# Schema.net
KiCad netlist of a schematic drawn in Altium Designer
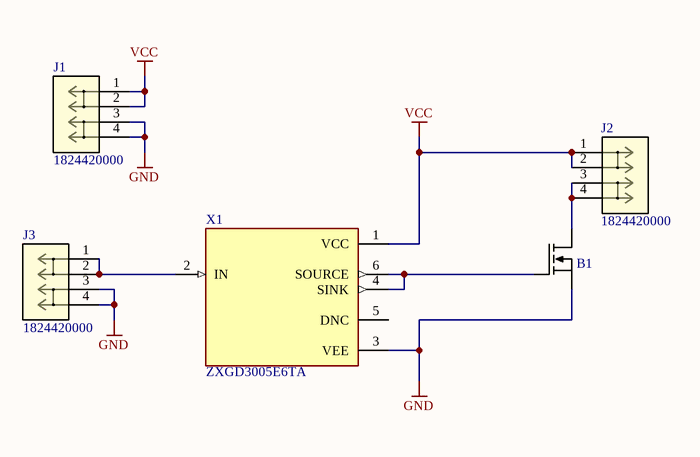
[diagram p0: Schema.SchDoc]

(export (version "E")
  (design (tool "Eeschema 10.0.6"))
  (components
    (comp (ref "B1")
      (value "N Kanal FET")
      (footprint "GeneralPCBLibrary:SOT23-3")
      (libsource (lib "GeneralSchemaLibrary") (part "N Kanal FET"))
    )
    (comp (ref "J1")
      (value "1824420000")
      (footprint "CONN2_1824420000_WED")
      (description "No Description Available")
      (fields (field (name "COPYRIGHT") "Copyright (C) 2021 Ultra Librarian. All rights reserved."))
      (libsource (lib "GeneralSchemaLibrary") (part "1824420000"))
    )
    (comp (ref "J2")
      (value "1824420000")
      (footprint "CONN2_1824420000_WED")
      (description "No Description Available")
      (fields (field (name "COPYRIGHT") "Copyright (C) 2021 Ultra Librarian. All rights reserved."))
      (libsource (lib "") (part "1824420000_1"))
    )
    (comp (ref "J3")
      (value "1824420000")
      (footprint "CONN2_1824420000_WED")
      (description "No Description Available")
      (fields (field (name "COPYRIGHT") "Copyright (C) 2021 Ultra Librarian. All rights reserved."))
      (libsource (lib "GeneralSchemaLibrary") (part "1824420000"))
    )
    (comp (ref "X1")
      (value "ZXGD3005E6TA")
      (footprint "GeneralPCBLibrary:SOT26")
      (description "Low-Side Gate Driver IC Non-Inverting SOT-26")
      (libsource (lib "GeneralSchemaLibrary") (part "ZXGD3005E6TA"))
    )
  )
  (nets
    (net (code "1") (name "GND") (class "Default")
      (node (ref "B1") (pin "2") (pinfunction "Source_2") (pintype "passive"))
      (node (ref "J1") (pin "3") (pinfunction "3_3") (pintype "passive"))
      (node (ref "J1") (pin "4") (pinfunction "4_4") (pintype "passive"))
      (node (ref "J3") (pin "3") (pinfunction "3_3") (pintype "passive"))
      (node (ref "J3") (pin "4") (pinfunction "4_4") (pintype "passive"))
      (node (ref "X1") (pin "3") (pinfunction "VEE_3") (pintype "power_in"))
    )
    (net (code "2") (name "Net-(B1-Drain)") (class "Default")
      (node (ref "B1") (pin "3") (pinfunction "Drain_3") (pintype "passive"))
      (node (ref "J2") (pin "3") (pinfunction "3_3") (pintype "passive"))
      (node (ref "J2") (pin "4") (pinfunction "4_4") (pintype "passive"))
    )
    (net (code "3") (name "Net-(B1-Gate)") (class "Default")
      (node (ref "B1") (pin "1") (pinfunction "Gate_1") (pintype "passive"))
      (node (ref "X1") (pin "4") (pinfunction "SINK_4") (pintype "output"))
      (node (ref "X1") (pin "6") (pinfunction "SOURCE_6") (pintype "output"))
    )
    (net (code "4") (name "Net-(X1-IN)") (class "Default")
      (node (ref "J3") (pin "1") (pinfunction "1_1") (pintype "passive"))
      (node (ref "J3") (pin "2") (pinfunction "2_2") (pintype "passive"))
      (node (ref "X1") (pin "2") (pinfunction "IN_2") (pintype "input"))
    )
    (net (code "5") (name "VCC") (class "Default")
      (node (ref "J1") (pin "1") (pinfunction "1_1") (pintype "passive"))
      (node (ref "J1") (pin "2") (pinfunction "2_2") (pintype "passive"))
      (node (ref "J2") (pin "1") (pinfunction "1_1") (pintype "passive"))
      (node (ref "J2") (pin "2") (pinfunction "2_2") (pintype "passive"))
      (node (ref "X1") (pin "1") (pinfunction "VCC_1") (pintype "power_in"))
    )
    (net (code "6") (name "unconnected-(X1-DNC-Pad5)") (class "Default")
      (node (ref "X1") (pin "5") (pinfunction "DNC_5") (pintype "passive"))
    )
  )
)
